# CPCIS_Connectors_P1_P6.net
KiCad netlist of a schematic drawn in Altium Designer
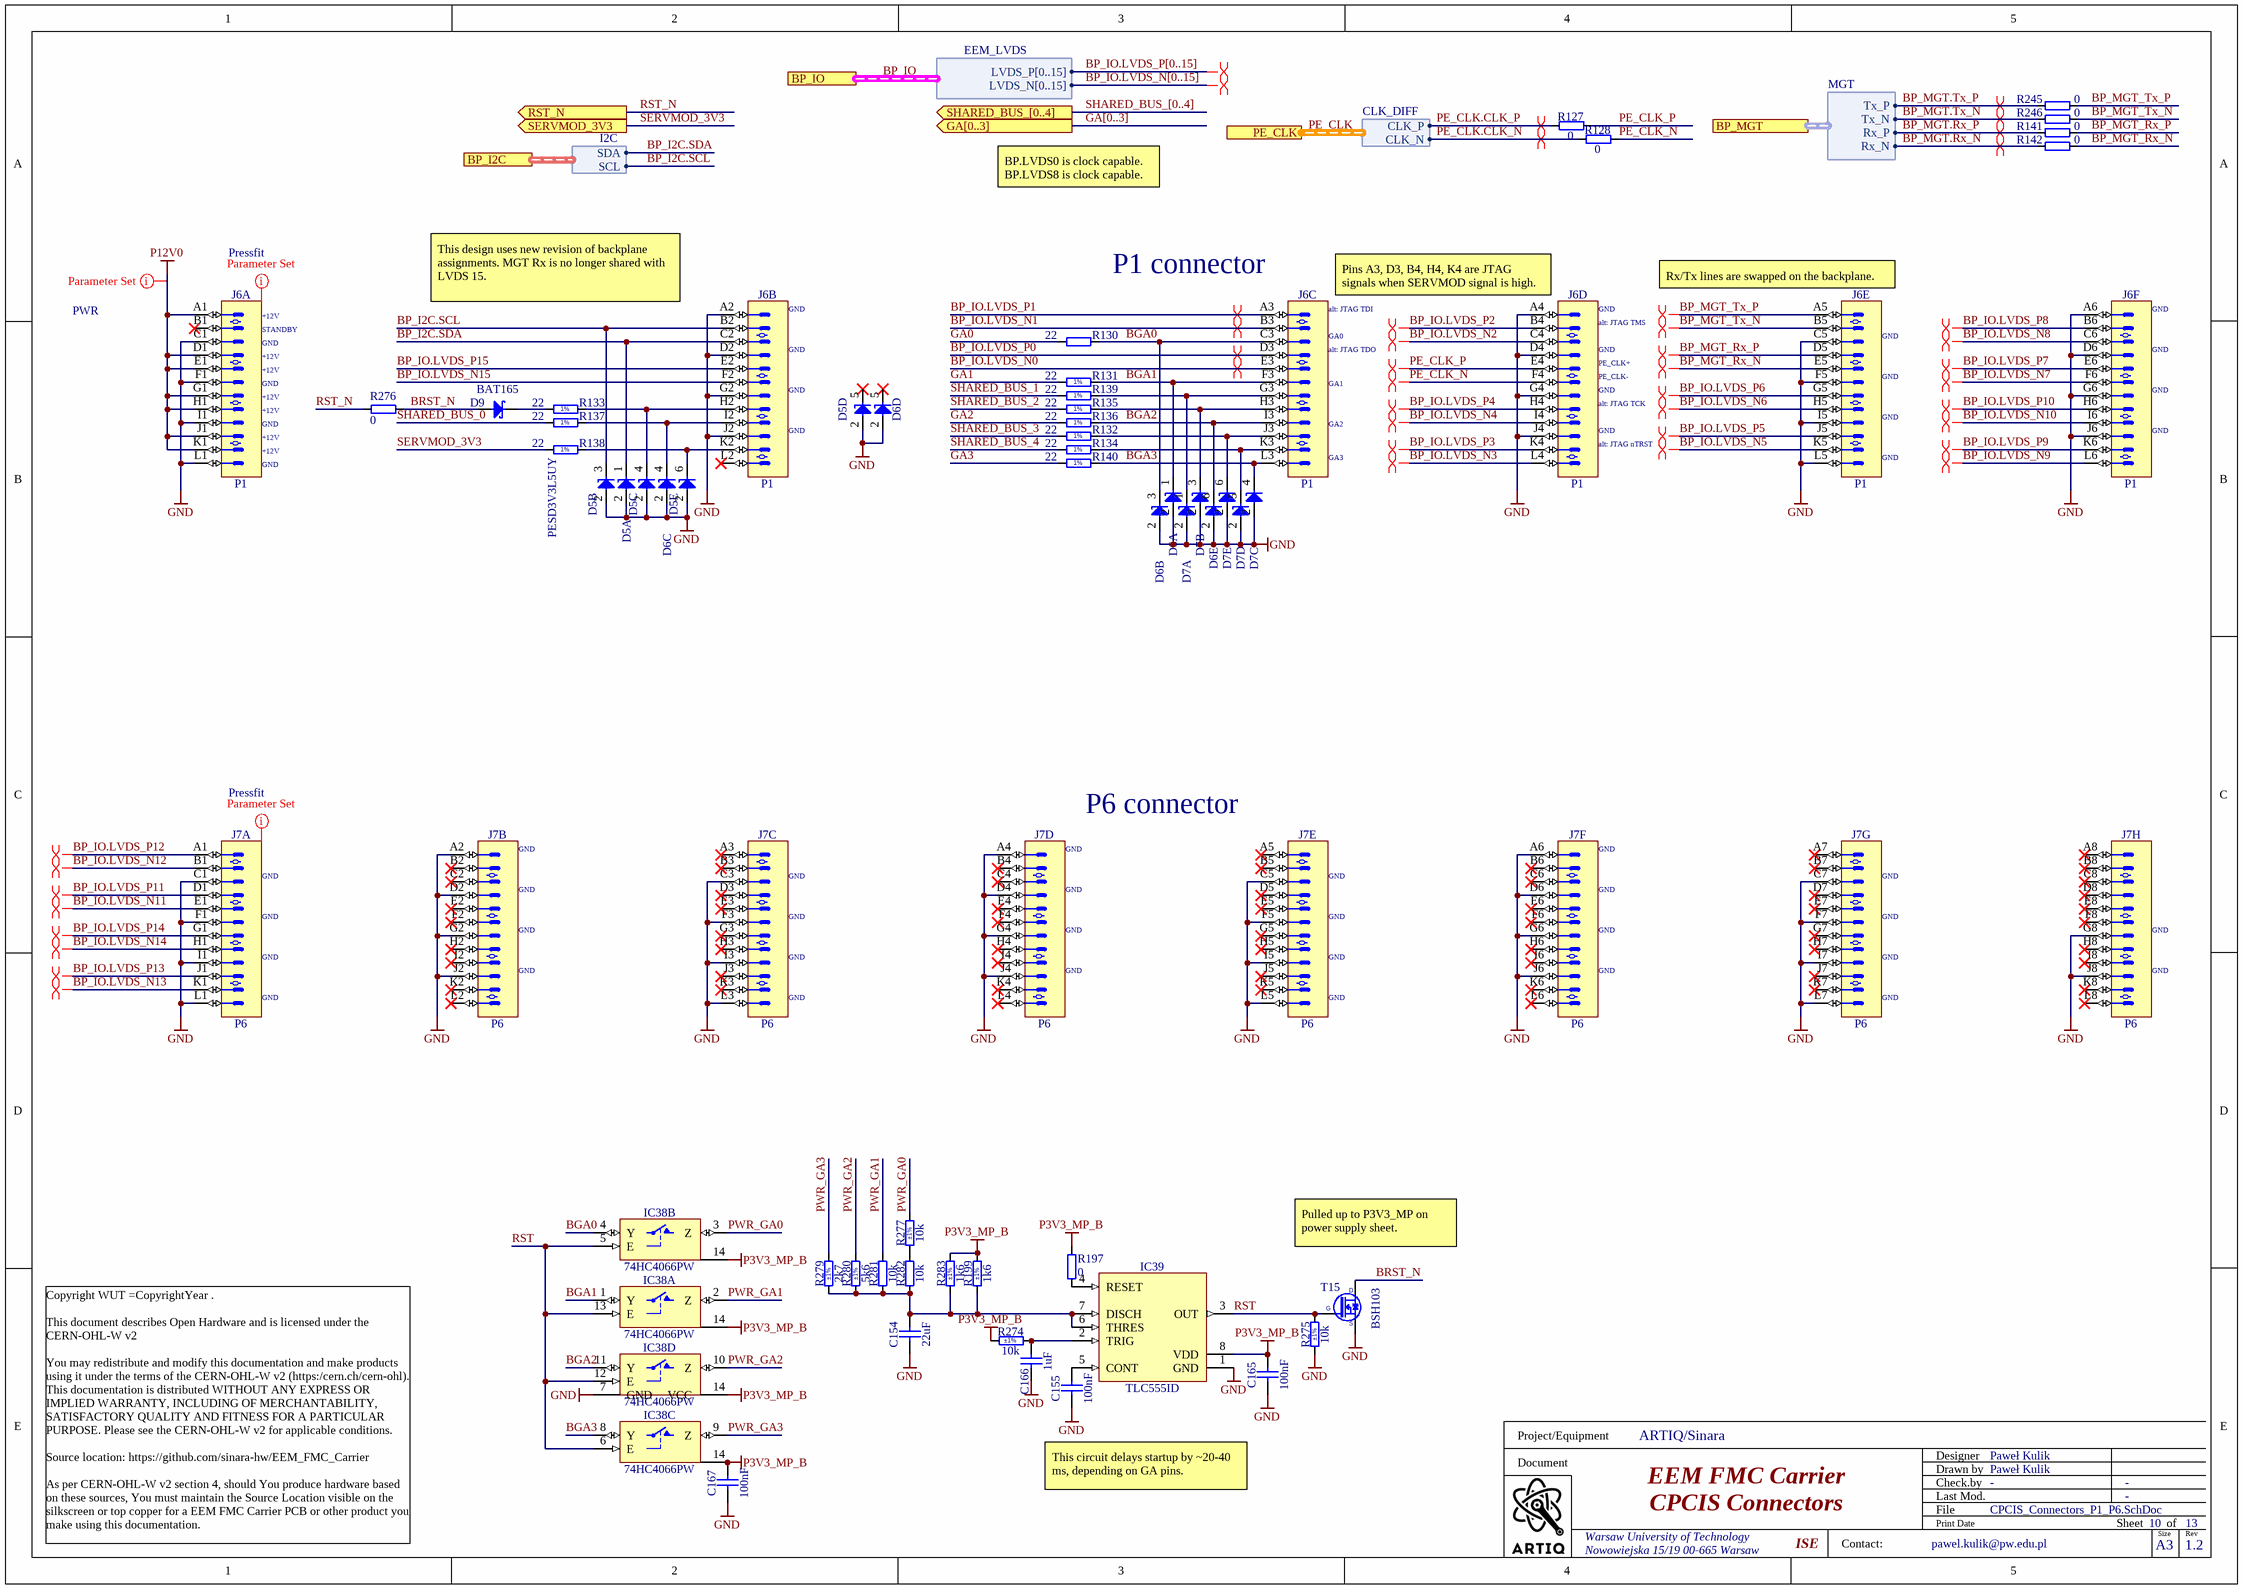
[diagram p0: CPCIS_Connectors_P1_P6.SchDoc]

(export (version "E")
  (design (tool "Eeschema 10.0.6"))
  (components
    (comp (ref "C154")
      (value "22uF")
      (footprint "CAPC1608X90N")
      (description "Non-polarised capacitor")
      (fields
        (field (name "MANUFACTURER") "GENERIC")
        (field (name "PART NUMBER") "CC0603_22UF_6.3V_20%_X5R")
        (field (name "AUTHOR") "CERN DEM JLC")
      )
      (libsource (lib "Capacitors") (part "Capacitor - non polarized"))
    )
    (comp (ref "C155")
      (value "100nF")
      (footprint "CAPC1005X55N")
      (description "Non-polarised capacitor")
      (fields
        (field (name "PART NUMBER") "CC0402_100NF_16V_10%_X5R")
        (field (name "VOLTAGE") "16V")
        (field (name "AUTHOR") "CERN DEM JLC")
      )
      (libsource (lib "Capacitors") (part "Capacitor - non polarized"))
    )
    (comp (ref "C165")
      (value "100nF")
      (footprint "CAPC1005X55N")
      (description "Non-polarised capacitor")
      (fields
        (field (name "PART NUMBER") "CC0402_100NF_16V_10%_X5R")
        (field (name "VOLTAGE") "16V")
        (field (name "AUTHOR") "CERN DEM JLC")
      )
      (libsource (lib "Capacitors") (part "Capacitor - non polarized"))
    )
    (comp (ref "C166")
      (value "1uF")
      (footprint "CAPC1005X55N")
      (description "Non-polarised capacitor")
      (fields
        (field (name "PART NUMBER") "CC0402_1UF_16V_10%_X5R")
        (field (name "VOLTAGE") "16V")
        (field (name "AUTHOR") "CERN DEM JLC")
      )
      (libsource (lib "Capacitors") (part "Capacitor - non polarized"))
    )
    (comp (ref "C167")
      (value "100nF")
      (footprint "CAPC1005X55N")
      (description "Non-polarised capacitor")
      (fields
        (field (name "PART NUMBER") "CC0402_100NF_16V_10%_X5R")
        (field (name "VOLTAGE") "16V")
        (field (name "AUTHOR") "CERN DEM JLC")
      )
      (libsource (lib "Capacitors") (part "Capacitor - non polarized"))
    )
    (comp (ref "D5")
      (value "PESD3V3L5UY")
      (footprint "SOT65P210X110-6N")
      (description "Fivefold ESD Protection Diode Arrays")
      (fields
        (field (name "VOLTAGE") "3.3V")
        (field (name "POWER") "200W")
        (field (name "AUTHOR") "CERN DEM WB")
      )
      (libsource (lib "ICs And Semiconductors") (part "PESD Array 5diodes 6pins Common anode2"))
    )
    (comp (ref "D6")
      (value "PESD3V3L5UY")
      (footprint "SOT65P210X110-6N")
      (description "Fivefold ESD Protection Diode Arrays")
      (fields
        (field (name "VOLTAGE") "3.3V")
        (field (name "POWER") "200W")
        (field (name "AUTHOR") "CERN DEM WB")
      )
      (libsource (lib "ICs And Semiconductors") (part "PESD Array 5diodes 6pins Common anode2"))
    )
    (comp (ref "D7")
      (value "PESD3V3L5UY")
      (footprint "SOT65P210X110-6N")
      (description "Fivefold ESD Protection Diode Arrays")
      (fields
        (field (name "VOLTAGE") "3.3V")
        (field (name "POWER") "200W")
        (field (name "AUTHOR") "CERN DEM WB")
      )
      (libsource (lib "ICs And Semiconductors") (part "PESD Array 5diodes 6pins Common anode2"))
    )
    (comp (ref "D9")
      (value "BAT165")
      (footprint "SOD2512X110N")
      (description "Schottky Diode")
      (fields
        (field (name "MANUFACTURER") "INFINEON")
        (field (name "VOLTAGE") "40V")
        (field (name "AUTHOR") "CERN DEM JLC")
      )
      (libsource (lib "ICs And Semiconductors") (part "Diode Schottky"))
    )
    (comp (ref "IC38")
      (value "74HC4066PW")
      (footprint "SOP65P640X110-14N")
      (fields (field (name "MANUFACTURER") "NXP SEMICONDUCTORS") (field (name "AUTHOR") "CERN DEM JLC"))
      (libsource (lib "ICs And Semiconductors") (part "4066"))
    )
    (comp (ref "IC39")
      (value "TLC555ID")
      (footprint "SOIC127P600X175-8N")
      (description "LinCMOS Timer")
      (fields (field (name "MANUFACTURER") "TEXAS INSTRUMENTS") (field (name "AUTHOR") "CERN DEM JMW"))
      (libsource (lib "ICs And Semiconductors") (part "TLC555"))
    )
    (comp (ref "J6")
      (value "P1")
      (footprint "AMPHENOL_10052825-101LF")
      (description "72 Contacts Header, 6 Columns, 4 Pairs per Column")
      (fields
        (field (name "PART NUMBER") "AMPHENOL_10052825-101LF")
        (field (name "MANUFACTURER") "AMPHENOL")
        (field (name "AUTHOR") "CERN DEM MR")
      )
      (libsource (lib "Connectors") (part "AMPHENOL_10052825-101LF"))
    )
    (comp (ref "J7")
      (value "P6")
      (footprint "AMPHENOL_10052838-101LF")
      (description "96 Contacts Header, 8 Columns, 4 Pairs per Column")
      (fields
        (field (name "PART NUMBER") "AMPHENOL_10052838-101LF")
        (field (name "MANUFACTURER") "AMPHENOL")
        (field (name "AUTHOR") "CERN DEM MR")
      )
      (libsource (lib "Connectors") (part "AMPHENOL_10052838-101LF"))
    )
    (comp (ref "R127")
      (value "0")
      (footprint "RESC0603X28N")
      (description "Resistor")
      (fields
        (field (name "PART NUMBER") "R0201_0R_JUMPER")
        (field (name "MANUFACTURER") "GENERIC")
        (field (name "AUTHOR") "CERN DEM JLC")
      )
      (libsource (lib "Resistors") (part "Resistor"))
    )
    (comp (ref "R128")
      (value "0")
      (footprint "RESC0603X28N")
      (description "Resistor")
      (fields
        (field (name "PART NUMBER") "R0201_0R_JUMPER")
        (field (name "MANUFACTURER") "GENERIC")
        (field (name "AUTHOR") "CERN DEM JLC")
      )
      (libsource (lib "Resistors") (part "Resistor"))
    )
    (comp (ref "R130")
      (value "22")
      (footprint "RESC1005X40N")
      (description "Resistor - 1%")
      (fields
        (field (name "PART NUMBER") "R0402_22R_1%_0.0625W_100PPM")
        (field (name "POWER") "0.0625W")
        (field (name "AUTHOR") "CERN DEM JLC")
      )
      (libsource (lib "Resistors") (part "Resistor - 1%"))
    )
    (comp (ref "R131")
      (value "22")
      (footprint "RESC1005X40N")
      (description "Resistor - 1%")
      (fields
        (field (name "PART NUMBER") "R0402_22R_1%_0.0625W_100PPM")
        (field (name "POWER") "0.0625W")
        (field (name "AUTHOR") "CERN DEM JLC")
      )
      (libsource (lib "Resistors") (part "Resistor - 1%"))
    )
    (comp (ref "R132")
      (value "22")
      (footprint "RESC1005X40N")
      (description "Resistor - 1%")
      (fields
        (field (name "PART NUMBER") "R0402_22R_1%_0.0625W_100PPM")
        (field (name "POWER") "0.0625W")
        (field (name "AUTHOR") "CERN DEM JLC")
      )
      (libsource (lib "Resistors") (part "Resistor - 1%"))
    )
    (comp (ref "R133")
      (value "22")
      (footprint "RESC1005X40N")
      (description "Resistor - 1%")
      (fields
        (field (name "PART NUMBER") "R0402_22R_1%_0.0625W_100PPM")
        (field (name "POWER") "0.0625W")
        (field (name "AUTHOR") "CERN DEM JLC")
      )
      (libsource (lib "Resistors") (part "Resistor - 1%"))
    )
    (comp (ref "R134")
      (value "22")
      (footprint "RESC1005X40N")
      (description "Resistor - 1%")
      (fields
        (field (name "PART NUMBER") "R0402_22R_1%_0.0625W_100PPM")
        (field (name "POWER") "0.0625W")
        (field (name "AUTHOR") "CERN DEM JLC")
      )
      (libsource (lib "Resistors") (part "Resistor - 1%"))
    )
    (comp (ref "R135")
      (value "22")
      (footprint "RESC1005X40N")
      (description "Resistor - 1%")
      (fields
        (field (name "PART NUMBER") "R0402_22R_1%_0.0625W_100PPM")
        (field (name "POWER") "0.0625W")
        (field (name "AUTHOR") "CERN DEM JLC")
      )
      (libsource (lib "Resistors") (part "Resistor - 1%"))
    )
    (comp (ref "R136")
      (value "22")
      (footprint "RESC1005X40N")
      (description "Resistor - 1%")
      (fields
        (field (name "PART NUMBER") "R0402_22R_1%_0.0625W_100PPM")
        (field (name "POWER") "0.0625W")
        (field (name "AUTHOR") "CERN DEM JLC")
      )
      (libsource (lib "Resistors") (part "Resistor - 1%"))
    )
    (comp (ref "R137")
      (value "22")
      (footprint "RESC1005X40N")
      (description "Resistor - 1%")
      (fields
        (field (name "PART NUMBER") "R0402_22R_1%_0.0625W_100PPM")
        (field (name "POWER") "0.0625W")
        (field (name "AUTHOR") "CERN DEM JLC")
      )
      (libsource (lib "Resistors") (part "Resistor - 1%"))
    )
    (comp (ref "R138")
      (value "22")
      (footprint "RESC1005X40N")
      (description "Resistor - 1%")
      (fields
        (field (name "PART NUMBER") "R0402_22R_1%_0.0625W_100PPM")
        (field (name "POWER") "0.0625W")
        (field (name "AUTHOR") "CERN DEM JLC")
      )
      (libsource (lib "Resistors") (part "Resistor - 1%"))
    )
    (comp (ref "R139")
      (value "22")
      (footprint "RESC1005X40N")
      (description "Resistor - 1%")
      (fields
        (field (name "PART NUMBER") "R0402_22R_1%_0.0625W_100PPM")
        (field (name "POWER") "0.0625W")
        (field (name "AUTHOR") "CERN DEM JLC")
      )
      (libsource (lib "Resistors") (part "Resistor - 1%"))
    )
    (comp (ref "R140")
      (value "22")
      (footprint "RESC1005X40N")
      (description "Resistor - 1%")
      (fields
        (field (name "PART NUMBER") "R0402_22R_1%_0.0625W_100PPM")
        (field (name "POWER") "0.0625W")
        (field (name "AUTHOR") "CERN DEM JLC")
      )
      (libsource (lib "Resistors") (part "Resistor - 1%"))
    )
    (comp (ref "R141")
      (value "0")
      (footprint "RESC0603X28N")
      (description "Resistor")
      (fields
        (field (name "PART NUMBER") "R0201_0R_JUMPER")
        (field (name "MANUFACTURER") "GENERIC")
        (field (name "AUTHOR") "CERN DEM JLC")
      )
      (libsource (lib "Resistors") (part "Resistor"))
    )
    (comp (ref "R142")
      (value "0")
      (footprint "RESC0603X28N")
      (description "Resistor")
      (fields
        (field (name "PART NUMBER") "R0201_0R_JUMPER")
        (field (name "MANUFACTURER") "GENERIC")
        (field (name "AUTHOR") "CERN DEM JLC")
      )
      (libsource (lib "Resistors") (part "Resistor"))
    )
    (comp (ref "R197")
      (value "0")
      (footprint "RESC1005X40N")
      (description "Resistor")
      (fields
        (field (name "PART NUMBER") "R0402_0R_JUMPER")
        (field (name "MANUFACTURER") "GENERIC")
        (field (name "AUTHOR") "CERN DEM JLC")
      )
      (libsource (lib "Resistors") (part "Resistor"))
    )
    (comp (ref "R199")
      (value "1k6")
      (footprint "RESC1005X40N")
      (description "Resistor - 1%")
      (fields
        (field (name "PART NUMBER") "R0402_1K6_1%_0.0625W_100PPM")
        (field (name "POWER") "0.0625W")
        (field (name "TOLERANCE") "±1%")
        (field (name "AUTHOR") "CERN DEM JLC")
      )
      (libsource (lib "Resistors") (part "Resistor - 1%"))
    )
    (comp (ref "R245")
      (value "0")
      (footprint "RESC0603X28N")
      (description "Resistor")
      (fields
        (field (name "PART NUMBER") "R0201_0R_JUMPER")
        (field (name "MANUFACTURER") "GENERIC")
        (field (name "AUTHOR") "CERN DEM JLC")
      )
      (libsource (lib "Resistors") (part "Resistor"))
    )
    (comp (ref "R246")
      (value "0")
      (footprint "RESC0603X28N")
      (description "Resistor")
      (fields
        (field (name "PART NUMBER") "R0201_0R_JUMPER")
        (field (name "MANUFACTURER") "GENERIC")
        (field (name "AUTHOR") "CERN DEM JLC")
      )
      (libsource (lib "Resistors") (part "Resistor"))
    )
    (comp (ref "R274")
      (value "10k")
      (footprint "RESC1005X40N")
      (description "Resistor - 1%")
      (fields
        (field (name "TOLERANCE") "±1%")
        (field (name "PART NUMBER") "R0402_10K_1%_0.0625W_100PPM")
        (field (name "POWER") "0.0625W")
        (field (name "AUTHOR") "CERN DEM JLC")
      )
      (libsource (lib "Resistors") (part "Resistor - 1%"))
    )
    (comp (ref "R275")
      (value "10k")
      (footprint "RESC1005X40N")
      (description "Resistor - 1%")
      (fields
        (field (name "TOLERANCE") "±1%")
        (field (name "PART NUMBER") "R0402_10K_1%_0.0625W_100PPM")
        (field (name "POWER") "0.0625W")
        (field (name "AUTHOR") "CERN DEM JLC")
      )
      (libsource (lib "Resistors") (part "Resistor - 1%"))
    )
    (comp (ref "R276")
      (value "0")
      (footprint "RESC1005X40N")
      (description "Resistor")
      (fields
        (field (name "PART NUMBER") "R0402_0R_JUMPER")
        (field (name "MANUFACTURER") "GENERIC")
        (field (name "AUTHOR") "CERN DEM JLC")
      )
      (libsource (lib "Resistors") (part "Resistor"))
    )
    (comp (ref "R277")
      (value "10k")
      (footprint "RESC1005X40N")
      (description "Resistor - 1%")
      (fields
        (field (name "PART NUMBER") "R0402_10K_1%_0.0625W_100PPM")
        (field (name "POWER") "0.0625W")
        (field (name "TOLERANCE") "±1%")
        (field (name "AUTHOR") "CERN DEM JLC")
      )
      (libsource (lib "Resistors") (part "Resistor - 1%"))
    )
    (comp (ref "R279")
      (value "2k7")
      (footprint "RESC1608X55N")
      (description "Resistor - 1%")
      (fields
        (field (name "PART NUMBER") "R0603_2K7_1%_0.1W_100PPM")
        (field (name "POWER") "0.1W")
        (field (name "TOLERANCE") "±1%")
        (field (name "AUTHOR") "CERN DEM JLC")
      )
      (libsource (lib "Resistors") (part "Resistor - 1%"))
    )
    (comp (ref "R280")
      (value "5k6")
      (footprint "RESC1005X40N")
      (description "Resistor - 1%")
      (fields
        (field (name "PART NUMBER") "R0402_5K6_1%_0.0625W_100PPM")
        (field (name "POWER") "0.0625W")
        (field (name "TOLERANCE") "±1%")
        (field (name "AUTHOR") "CERN DEM JLC")
      )
      (libsource (lib "Resistors") (part "Resistor - 1%"))
    )
    (comp (ref "R281")
      (value "10k")
      (footprint "RESC1005X40N")
      (description "Resistor - 1%")
      (fields
        (field (name "PART NUMBER") "R0402_10K_1%_0.0625W_100PPM")
        (field (name "POWER") "0.0625W")
        (field (name "AUTHOR") "CERN DEM JLC")
      )
      (libsource (lib "Resistors") (part "Resistor - 1%"))
    )
    (comp (ref "R282")
      (value "10k")
      (footprint "RESC1005X40N")
      (description "Resistor - 1%")
      (fields
        (field (name "PART NUMBER") "R0402_10K_1%_0.0625W_100PPM")
        (field (name "POWER") "0.0625W")
        (field (name "AUTHOR") "CERN DEM JLC")
      )
      (libsource (lib "Resistors") (part "Resistor - 1%"))
    )
    (comp (ref "R283")
      (value "1k6")
      (footprint "RESC1005X40N")
      (description "Resistor - 1%")
      (fields
        (field (name "PART NUMBER") "R0402_1K6_1%_0.0625W_100PPM")
        (field (name "POWER") "0.0625W")
        (field (name "TOLERANCE") "±1%")
        (field (name "AUTHOR") "CERN DEM JLC")
      )
      (libsource (lib "Resistors") (part "Resistor - 1%"))
    )
    (comp (ref "T15")
      (value "BSH103")
      (footprint "SOT95P230X110-3N")
      (description "N-CHANNEL MOSFET WITH DIODE")
      (fields (field (name "MANUFACTURER") "NEXPERIA") (field (name "AUTHOR") "CERN DEM JLC"))
      (libsource (lib "ICs And Semiconductors") (part "N-MOSFET-D 1G 2S 3D"))
    )
  )
  (nets
    (net (code "5") (name "/BGA0") (class "Default")
      (node (ref "D6") (pin "3") (pinfunction "C_3") (pintype "passive"))
      (node (ref "IC38") (pin "4") (pinfunction "Y_4") (pintype "bidirectional"))
      (node (ref "J6") (pin "C3") (pinfunction "C3_C3") (pintype "bidirectional"))
      (node (ref "R130") (pin "2") (pinfunction "2_2") (pintype "passive"))
    )
    (net (code "6") (name "/BGA1") (class "Default")
      (node (ref "D6") (pin "1") (pinfunction "C_1") (pintype "passive"))
      (node (ref "IC38") (pin "1") (pinfunction "Y_1") (pintype "bidirectional"))
      (node (ref "J6") (pin "F3") (pinfunction "F3_F3") (pintype "bidirectional"))
      (node (ref "R131") (pin "2") (pinfunction "2_2") (pintype "passive"))
    )
    (net (code "7") (name "/BGA2") (class "Default")
      (node (ref "D6") (pin "6") (pinfunction "C_6") (pintype "passive"))
      (node (ref "IC38") (pin "11") (pinfunction "Y_11") (pintype "bidirectional"))
      (node (ref "J6") (pin "I3") (pinfunction "I3_I3") (pintype "bidirectional"))
      (node (ref "R136") (pin "2") (pinfunction "2_2") (pintype "passive"))
    )
    (net (code "8") (name "/BGA3") (class "Default")
      (node (ref "D7") (pin "4") (pinfunction "C_4") (pintype "passive"))
      (node (ref "IC38") (pin "8") (pinfunction "Y_8") (pintype "bidirectional"))
      (node (ref "J6") (pin "L3") (pinfunction "L3_L3") (pintype "bidirectional"))
      (node (ref "R140") (pin "2") (pinfunction "2_2") (pintype "passive"))
    )
    (net (code "9") (name "/BP_I2C.SCL") (class "Default")
      (node (ref "D5") (pin "3") (pinfunction "C_3") (pintype "passive"))
      (node (ref "J6") (pin "B2") (pinfunction "B2_B2") (pintype "bidirectional"))
    )
    (net (code "10") (name "/BP_I2C.SDA") (class "Default")
      (node (ref "D5") (pin "1") (pinfunction "C_1") (pintype "passive"))
      (node (ref "J6") (pin "C2") (pinfunction "C2_C2") (pintype "bidirectional"))
    )
    (net (code "11") (name "/BP_IO.LVDS_N0") (class "Default")
      (node (ref "J6") (pin "E3") (pinfunction "E3_E3") (pintype "bidirectional"))
    )
    (net (code "12") (name "/BP_IO.LVDS_N1") (class "Default")
      (node (ref "J6") (pin "B3") (pinfunction "B3_B3") (pintype "bidirectional"))
    )
    (net (code "13") (name "/BP_IO.LVDS_N2") (class "Default")
      (node (ref "J6") (pin "C4") (pinfunction "C4_C4") (pintype "bidirectional"))
    )
    (net (code "14") (name "/BP_IO.LVDS_N3") (class "Default")
      (node (ref "J6") (pin "L4") (pinfunction "L4_L4") (pintype "bidirectional"))
    )
    (net (code "15") (name "/BP_IO.LVDS_N4") (class "Default")
      (node (ref "J6") (pin "I4") (pinfunction "I4_I4") (pintype "bidirectional"))
    )
    (net (code "16") (name "/BP_IO.LVDS_N5") (class "Default")
      (node (ref "J6") (pin "K5") (pinfunction "K5_K5") (pintype "bidirectional"))
    )
    (net (code "17") (name "/BP_IO.LVDS_N6") (class "Default")
      (node (ref "J6") (pin "H5") (pinfunction "H5_H5") (pintype "bidirectional"))
    )
    (net (code "18") (name "/BP_IO.LVDS_N7") (class "Default")
      (node (ref "J6") (pin "F6") (pinfunction "F6_F6") (pintype "bidirectional"))
    )
    (net (code "19") (name "/BP_IO.LVDS_N8") (class "Default")
      (node (ref "J6") (pin "C6") (pinfunction "C6_C6") (pintype "bidirectional"))
    )
    (net (code "20") (name "/BP_IO.LVDS_N9") (class "Default")
      (node (ref "J6") (pin "L6") (pinfunction "L6_L6") (pintype "bidirectional"))
    )
    (net (code "21") (name "/BP_IO.LVDS_N10") (class "Default")
      (node (ref "J6") (pin "I6") (pinfunction "I6_I6") (pintype "bidirectional"))
    )
    (net (code "22") (name "/BP_IO.LVDS_N11") (class "Default")
      (node (ref "J7") (pin "E1") (pinfunction "E1_E1") (pintype "bidirectional"))
    )
    (net (code "23") (name "/BP_IO.LVDS_N12") (class "Default")
      (node (ref "J7") (pin "B1") (pinfunction "B1_B1") (pintype "bidirectional"))
    )
    (net (code "24") (name "/BP_IO.LVDS_N13") (class "Default")
      (node (ref "J7") (pin "K1") (pinfunction "K1_K1") (pintype "bidirectional"))
    )
    (net (code "25") (name "/BP_IO.LVDS_N14") (class "Default")
      (node (ref "J7") (pin "H1") (pinfunction "H1_H1") (pintype "bidirectional"))
    )
    (net (code "26") (name "/BP_IO.LVDS_N15") (class "Default")
      (node (ref "J6") (pin "F2") (pinfunction "F2_F2") (pintype "bidirectional"))
    )
    (net (code "28") (name "/BP_IO.LVDS_P0") (class "Default")
      (node (ref "J6") (pin "D3") (pinfunction "D3_D3") (pintype "bidirectional"))
    )
    (net (code "29") (name "/BP_IO.LVDS_P1") (class "Default")
      (node (ref "J6") (pin "A3") (pinfunction "A3_A3") (pintype "bidirectional"))
    )
    (net (code "30") (name "/BP_IO.LVDS_P2") (class "Default")
      (node (ref "J6") (pin "B4") (pinfunction "B4_B4") (pintype "bidirectional"))
    )
    (net (code "31") (name "/BP_IO.LVDS_P3") (class "Default")
      (node (ref "J6") (pin "K4") (pinfunction "K4_K4") (pintype "bidirectional"))
    )
    (net (code "32") (name "/BP_IO.LVDS_P4") (class "Default")
      (node (ref "J6") (pin "H4") (pinfunction "H4_H4") (pintype "bidirectional"))
    )
    (net (code "33") (name "/BP_IO.LVDS_P5") (class "Default")
      (node (ref "J6") (pin "J5") (pinfunction "J5_J5") (pintype "bidirectional"))
    )
    (net (code "34") (name "/BP_IO.LVDS_P6") (class "Default")
      (node (ref "J6") (pin "G5") (pinfunction "G5_G5") (pintype "bidirectional"))
    )
    (net (code "35") (name "/BP_IO.LVDS_P7") (class "Default")
      (node (ref "J6") (pin "E6") (pinfunction "E6_E6") (pintype "bidirectional"))
    )
    (net (code "36") (name "/BP_IO.LVDS_P8") (class "Default")
      (node (ref "J6") (pin "B6") (pinfunction "B6_B6") (pintype "bidirectional"))
    )
    (net (code "37") (name "/BP_IO.LVDS_P9") (class "Default")
      (node (ref "J6") (pin "K6") (pinfunction "K6_K6") (pintype "bidirectional"))
    )
    (net (code "38") (name "/BP_IO.LVDS_P10") (class "Default")
      (node (ref "J6") (pin "H6") (pinfunction "H6_H6") (pintype "bidirectional"))
    )
    (net (code "39") (name "/BP_IO.LVDS_P11") (class "Default")
      (node (ref "J7") (pin "D1") (pinfunction "D1_D1") (pintype "bidirectional"))
    )
    (net (code "40") (name "/BP_IO.LVDS_P12") (class "Default")
      (node (ref "J7") (pin "A1") (pinfunction "A1_A1") (pintype "bidirectional"))
    )
    (net (code "41") (name "/BP_IO.LVDS_P13") (class "Default")
      (node (ref "J7") (pin "J1") (pinfunction "J1_J1") (pintype "bidirectional"))
    )
    (net (code "42") (name "/BP_IO.LVDS_P14") (class "Default")
      (node (ref "J7") (pin "G1") (pinfunction "G1_G1") (pintype "bidirectional"))
    )
    (net (code "43") (name "/BP_IO.LVDS_P15") (class "Default")
      (node (ref "J6") (pin "E2") (pinfunction "E2_E2") (pintype "bidirectional"))
    )
    (net (code "44") (name "/BP_MGT.Rx_N") (class "Default")
      (node (ref "R142") (pin "1") (pinfunction "1_1") (pintype "passive"))
    )
    (net (code "45") (name "/BP_MGT.Rx_P") (class "Default")
      (node (ref "R141") (pin "1") (pinfunction "1_1") (pintype "passive"))
    )
    (net (code "46") (name "/BP_MGT.Tx_N") (class "Default")
      (node (ref "R246") (pin "1") (pinfunction "1_1") (pintype "passive"))
    )
    (net (code "47") (name "/BP_MGT.Tx_P") (class "Default")
      (node (ref "R245") (pin "1") (pinfunction "1_1") (pintype "passive"))
    )
    (net (code "48") (name "/BP_MGT_Rx_N") (class "Default")
      (node (ref "J6") (pin "E5") (pinfunction "E5_E5") (pintype "bidirectional"))
      (node (ref "R142") (pin "2") (pinfunction "2_2") (pintype "passive"))
    )
    (net (code "49") (name "/BP_MGT_Rx_P") (class "Default")
      (node (ref "J6") (pin "D5") (pinfunction "D5_D5") (pintype "bidirectional"))
      (node (ref "R141") (pin "2") (pinfunction "2_2") (pintype "passive"))
    )
    (net (code "50") (name "/BP_MGT_Tx_N") (class "Default")
      (node (ref "J6") (pin "B5") (pinfunction "B5_B5") (pintype "bidirectional"))
      (node (ref "R246") (pin "2") (pinfunction "2_2") (pintype "passive"))
    )
    (net (code "51") (name "/BP_MGT_Tx_P") (class "Default")
      (node (ref "J6") (pin "A5") (pinfunction "A5_A5") (pintype "bidirectional"))
      (node (ref "R245") (pin "2") (pinfunction "2_2") (pintype "passive"))
    )
    (net (code "52") (name "/BRST_N") (class "Default")
      (node (ref "D9") (pin "2") (pinfunction "A_2") (pintype "passive"))
      (node (ref "R276") (pin "1") (pinfunction "1_1") (pintype "passive"))
      (node (ref "T15") (pin "3") (pinfunction "D_3") (pintype "passive"))
    )
    (net (code "53") (name "/GA0") (class "Default")
      (node (ref "R130") (pin "1") (pinfunction "1_1") (pintype "passive"))
    )
    (net (code "54") (name "/GA1") (class "Default")
      (node (ref "R131") (pin "1") (pinfunction "1_1") (pintype "passive"))
    )
    (net (code "55") (name "/GA2") (class "Default")
      (node (ref "R136") (pin "1") (pinfunction "1_1") (pintype "passive"))
    )
    (net (code "56") (name "/GA3") (class "Default")
      (node (ref "R140") (pin "1") (pinfunction "1_1") (pintype "passive"))
    )
    (net (code "58") (name "/PE_CLK.CLK_N") (class "Default")
      (node (ref "R128") (pin "1") (pinfunction "1_1") (pintype "passive"))
    )
    (net (code "59") (name "/PE_CLK.CLK_P") (class "Default")
      (node (ref "R127") (pin "1") (pinfunction "1_1") (pintype "passive"))
    )
    (net (code "60") (name "/PE_CLK_N") (class "Default")
      (node (ref "J6") (pin "F4") (pinfunction "F4_F4") (pintype "bidirectional"))
      (node (ref "R128") (pin "2") (pinfunction "2_2") (pintype "passive"))
    )
    (net (code "61") (name "/PE_CLK_P") (class "Default")
      (node (ref "J6") (pin "E4") (pinfunction "E4_E4") (pintype "bidirectional"))
      (node (ref "R127") (pin "2") (pinfunction "2_2") (pintype "passive"))
    )
    (net (code "63") (name "/PWR_GA0") (class "Default")
      (node (ref "IC38") (pin "3") (pinfunction "Z_3") (pintype "bidirectional"))
      (node (ref "R277") (pin "2") (pinfunction "2_2") (pintype "passive"))
    )
    (net (code "64") (name "/PWR_GA1") (class "Default")
      (node (ref "IC38") (pin "2") (pinfunction "Z_2") (pintype "bidirectional"))
      (node (ref "R281") (pin "2") (pinfunction "2_2") (pintype "passive"))
    )
    (net (code "65") (name "/PWR_GA2") (class "Default")
      (node (ref "IC38") (pin "10") (pinfunction "Z_10") (pintype "bidirectional"))
      (node (ref "R280") (pin "2") (pinfunction "2_2") (pintype "passive"))
    )
    (net (code "66") (name "/PWR_GA3") (class "Default")
      (node (ref "IC38") (pin "9") (pinfunction "Z_9") (pintype "bidirectional"))
      (node (ref "R279") (pin "2") (pinfunction "2_2") (pintype "passive"))
    )
    (net (code "67") (name "/RST") (class "Default")
      (node (ref "IC38") (pin "12") (pinfunction "E_12") (pintype "input"))
      (node (ref "IC38") (pin "13") (pinfunction "E_13") (pintype "input"))
      (node (ref "IC38") (pin "5") (pinfunction "E_5") (pintype "input"))
      (node (ref "IC38") (pin "6") (pinfunction "E_6") (pintype "input"))
      (node (ref "IC39") (pin "3") (pinfunction "OUT_3") (pintype "output"))
      (node (ref "R275") (pin "2") (pinfunction "2_2") (pintype "passive"))
      (node (ref "T15") (pin "1") (pinfunction "G_1") (pintype "passive"))
    )
    (net (code "68") (name "/RST_N") (class "Default")
      (node (ref "R276") (pin "2") (pinfunction "2_2") (pintype "passive"))
    )
    (net (code "69") (name "/SERVMOD_3V3") (class "Default")
      (node (ref "R138") (pin "1") (pinfunction "1_1") (pintype "passive"))
    )
    (net (code "70") (name "/SHARED_BUS_0") (class "Default")
      (node (ref "R137") (pin "1") (pinfunction "1_1") (pintype "passive"))
    )
    (net (code "71") (name "/SHARED_BUS_1") (class "Default")
      (node (ref "R139") (pin "1") (pinfunction "1_1") (pintype "passive"))
    )
    (net (code "72") (name "/SHARED_BUS_2") (class "Default")
      (node (ref "R135") (pin "1") (pinfunction "1_1") (pintype "passive"))
    )
    (net (code "73") (name "/SHARED_BUS_3") (class "Default")
      (node (ref "R132") (pin "1") (pinfunction "1_1") (pintype "passive"))
    )
    (net (code "74") (name "/SHARED_BUS_4") (class "Default")
      (node (ref "R134") (pin "1") (pinfunction "1_1") (pintype "passive"))
    )
    (net (code "80") (name "GND") (class "Default")
      (node (ref "C154") (pin "1") (pinfunction "1_1") (pintype "passive"))
      (node (ref "C155") (pin "1") (pinfunction "1_1") (pintype "passive"))
      (node (ref "C165") (pin "1") (pinfunction "1_1") (pintype "passive"))
      (node (ref "C166") (pin "1") (pinfunction "1_1") (pintype "passive"))
      (node (ref "C167") (pin "1") (pinfunction "1_1") (pintype "passive"))
      (node (ref "D5") (pin "2") (pinfunction "A_2") (pintype "passive"))
      (node (ref "D6") (pin "2") (pinfunction "A_2") (pintype "passive"))
      (node (ref "D7") (pin "2") (pinfunction "A_2") (pintype "passive"))
      (node (ref "IC38") (pin "7") (pinfunction "GND_7") (pintype "power_in"))
      (node (ref "IC39") (pin "1") (pinfunction "GND_1") (pintype "power_in"))
      (node (ref "J6") (pin "A2") (pinfunction "A2_A2") (pintype "bidirectional"))
      (node (ref "J6") (pin "A4") (pinfunction "A4_A4") (pintype "bidirectional"))
      (node (ref "J6") (pin "A6") (pinfunction "A6_A6") (pintype "bidirectional"))
      (node (ref "J6") (pin "C1") (pinfunction "C1_C1") (pintype "bidirectional"))
      (node (ref "J6") (pin "C5") (pinfunction "C5_C5") (pintype "bidirectional"))
      (node (ref "J6") (pin "D2") (pinfunction "D2_D2") (pintype "bidirectional"))
      (node (ref "J6") (pin "D4") (pinfunction "D4_D4") (pintype "bidirectional"))
      (node (ref "J6") (pin "D6") (pinfunction "D6_D6") (pintype "bidirectional"))
      (node (ref "J6") (pin "F1") (pinfunction "F1_F1") (pintype "bidirectional"))
      (node (ref "J6") (pin "F5") (pinfunction "F5_F5") (pintype "bidirectional"))
      (node (ref "J6") (pin "G2") (pinfunction "G2_G2") (pintype "bidirectional"))
      (node (ref "J6") (pin "G4") (pinfunction "G4_G4") (pintype "bidirectional"))
      (node (ref "J6") (pin "G6") (pinfunction "G6_G6") (pintype "bidirectional"))
      (node (ref "J6") (pin "I1") (pinfunction "I1_I1") (pintype "bidirectional"))
      (node (ref "J6") (pin "I5") (pinfunction "I5_I5") (pintype "bidirectional"))
      (node (ref "J6") (pin "J2") (pinfunction "J2_J2") (pintype "bidirectional"))
      (node (ref "J6") (pin "J4") (pinfunction "J4_J4") (pintype "bidirectional"))
      (node (ref "J6") (pin "J6") (pinfunction "J6_J6") (pintype "bidirectional"))
      (node (ref "J6") (pin "L1") (pinfunction "L1_L1") (pintype "bidirectional"))
      (node (ref "J6") (pin "L5") (pinfunction "L5_L5") (pintype "bidirectional"))
      (node (ref "J7") (pin "A2") (pinfunction "A2_A2") (pintype "bidirectional"))
      (node (ref "J7") (pin "A4") (pinfunction "A4_A4") (pintype "bidirectional"))
      (node (ref "J7") (pin "A6") (pinfunction "A6_A6") (pintype "bidirectional"))
      (node (ref "J7") (pin "C1") (pinfunction "C1_C1") (pintype "bidirectional"))
      (node (ref "J7") (pin "C3") (pinfunction "C3_C3") (pintype "bidirectional"))
      (node (ref "J7") (pin "C5") (pinfunction "C5_C5") (pintype "bidirectional"))
      (node (ref "J7") (pin "C7") (pinfunction "C7_C7") (pintype "bidirectional"))
      (node (ref "J7") (pin "D2") (pinfunction "D2_D2") (pintype "bidirectional"))
      (node (ref "J7") (pin "D4") (pinfunction "D4_D4") (pintype "bidirectional"))
      (node (ref "J7") (pin "D6") (pinfunction "D6_D6") (pintype "bidirectional"))
      (node (ref "J7") (pin "F1") (pinfunction "F1_F1") (pintype "bidirectional"))
      (node (ref "J7") (pin "F3") (pinfunction "F3_F3") (pintype "bidirectional"))
      (node (ref "J7") (pin "F5") (pinfunction "F5_F5") (pintype "bidirectional"))
      (node (ref "J7") (pin "F7") (pinfunction "F7_F7") (pintype "bidirectional"))
      (node (ref "J7") (pin "G2") (pinfunction "G2_G2") (pintype "bidirectional"))
      (node (ref "J7") (pin "G4") (pinfunction "G4_G4") (pintype "bidirectional"))
      (node (ref "J7") (pin "G6") (pinfunction "G6_G6") (pintype "bidirectional"))
      (node (ref "J7") (pin "G8") (pinfunction "G8_G8") (pintype "bidirectional"))
      (node (ref "J7") (pin "I1") (pinfunction "I1_I1") (pintype "bidirectional"))
      (node (ref "J7") (pin "I3") (pinfunction "I3_I3") (pintype "bidirectional"))
      (node (ref "J7") (pin "I5") (pinfunction "I5_I5") (pintype "bidirectional"))
      (node (ref "J7") (pin "I7") (pinfunction "I7_I7") (pintype "bidirectional"))
      (node (ref "J7") (pin "J2") (pinfunction "J2_J2") (pintype "bidirectional"))
      (node (ref "J7") (pin "J4") (pinfunction "J4_J4") (pintype "bidirectional"))
      (node (ref "J7") (pin "J6") (pinfunction "J6_J6") (pintype "bidirectional"))
      (node (ref "J7") (pin "J8") (pinfunction "J8_J8") (pintype "bidirectional"))
      (node (ref "J7") (pin "L1") (pinfunction "L1_L1") (pintype "bidirectional"))
      (node (ref "J7") (pin "L3") (pinfunction "L3_L3") (pintype "bidirectional"))
      (node (ref "J7") (pin "L5") (pinfunction "L5_L5") (pintype "bidirectional"))
      (node (ref "J7") (pin "L7") (pinfunction "L7_L7") (pintype "bidirectional"))
      (node (ref "R275") (pin "1") (pinfunction "1_1") (pintype "passive"))
      (node (ref "T15") (pin "2") (pinfunction "S_2") (pintype "passive"))
    )
    (net (code "81") (name "Net-(D5C-C)") (class "Default")
      (node (ref "D5") (pin "4") (pinfunction "C_4") (pintype "passive"))
      (node (ref "J6") (pin "H2") (pinfunction "H2_H2") (pintype "bidirectional"))
      (node (ref "R133") (pin "2") (pinfunction "2_2") (pintype "passive"))
    )
    (net (code "82") (name "Net-(D5E-C)") (class "Default")
      (node (ref "D5") (pin "6") (pinfunction "C_6") (pintype "passive"))
      (node (ref "J6") (pin "K2") (pinfunction "K2_K2") (pintype "bidirectional"))
      (node (ref "R138") (pin "2") (pinfunction "2_2") (pintype "passive"))
    )
    (net (code "83") (name "Net-(D6C-C)") (class "Default")
      (node (ref "D6") (pin "4") (pinfunction "C_4") (pintype "passive"))
      (node (ref "J6") (pin "I2") (pinfunction "I2_I2") (pintype "bidirectional"))
      (node (ref "R137") (pin "2") (pinfunction "2_2") (pintype "passive"))
    )
    (net (code "84") (name "Net-(D7A-C)") (class "Default")
      (node (ref "D7") (pin "1") (pinfunction "C_1") (pintype "passive"))
      (node (ref "J6") (pin "G3") (pinfunction "G3_G3") (pintype "bidirectional"))
      (node (ref "R139") (pin "2") (pinfunction "2_2") (pintype "passive"))
    )
    (net (code "85") (name "Net-(D7B-C)") (class "Default")
      (node (ref "D7") (pin "3") (pinfunction "C_3") (pintype "passive"))
      (node (ref "J6") (pin "H3") (pinfunction "H3_H3") (pintype "bidirectional"))
      (node (ref "R135") (pin "2") (pinfunction "2_2") (pintype "passive"))
    )
    (net (code "86") (name "Net-(D7D-C)") (class "Default")
      (node (ref "D7") (pin "5") (pinfunction "C_5") (pintype "passive"))
      (node (ref "J6") (pin "K3") (pinfunction "K3_K3") (pintype "bidirectional"))
      (node (ref "R134") (pin "2") (pinfunction "2_2") (pintype "passive"))
    )
    (net (code "87") (name "Net-(D7E-C)") (class "Default")
      (node (ref "D7") (pin "6") (pinfunction "C_6") (pintype "passive"))
      (node (ref "J6") (pin "J3") (pinfunction "J3_J3") (pintype "bidirectional"))
      (node (ref "R132") (pin "2") (pinfunction "2_2") (pintype "passive"))
    )
    (net (code "88") (name "Net-(D9-C)") (class "Default")
      (node (ref "D9") (pin "1") (pinfunction "C_1") (pintype "passive"))
      (node (ref "R133") (pin "1") (pinfunction "1_1") (pintype "passive"))
    )
    (net (code "89") (name "Net-(IC39-CONT)") (class "Default")
      (node (ref "C155") (pin "2") (pinfunction "2_2") (pintype "passive"))
      (node (ref "IC39") (pin "5") (pinfunction "CONT_5") (pintype "input"))
    )
    (net (code "90") (name "Net-(IC39-DISCH)") (class "Default")
      (node (ref "C154") (pin "2") (pinfunction "2_2") (pintype "passive"))
      (node (ref "IC39") (pin "6") (pinfunction "THRES_6") (pintype "input"))
      (node (ref "IC39") (pin "7") (pinfunction "DISCH_7") (pintype "input"))
      (node (ref "R199") (pin "1") (pinfunction "1_1") (pintype "passive"))
      (node (ref "R279") (pin "1") (pinfunction "1_1") (pintype "passive"))
      (node (ref "R280") (pin "1") (pinfunction "1_1") (pintype "passive"))
      (node (ref "R281") (pin "1") (pinfunction "1_1") (pintype "passive"))
      (node (ref "R282") (pin "1") (pinfunction "1_1") (pintype "passive"))
      (node (ref "R283") (pin "1") (pinfunction "1_1") (pintype "passive"))
    )
    (net (code "91") (name "Net-(IC39-RESET)") (class "Default")
      (node (ref "IC39") (pin "4") (pinfunction "RESET_4") (pintype "input"))
      (node (ref "R197") (pin "1") (pinfunction "1_1") (pintype "passive"))
    )
    (net (code "92") (name "Net-(IC39-TRIG)") (class "Default")
      (node (ref "C166") (pin "2") (pinfunction "2_2") (pintype "passive"))
      (node (ref "IC39") (pin "2") (pinfunction "TRIG_2") (pintype "input"))
      (node (ref "R274") (pin "2") (pinfunction "2_2") (pintype "passive"))
    )
    (net (code "93") (name "Net-(R277-Pad1)") (class "Default")
      (node (ref "R277") (pin "1") (pinfunction "1_1") (pintype "passive"))
      (node (ref "R282") (pin "2") (pinfunction "2_2") (pintype "passive"))
    )
    (net (code "94") (name "P3V3_MP_B") (class "Default")
      (node (ref "C165") (pin "2") (pinfunction "2_2") (pintype "passive"))
      (node (ref "C167") (pin "2") (pinfunction "2_2") (pintype "passive"))
      (node (ref "IC38") (pin "14") (pinfunction "VCC_14") (pintype "power_in"))
      (node (ref "IC39") (pin "8") (pinfunction "VDD_8") (pintype "power_in"))
      (node (ref "R197") (pin "2") (pinfunction "2_2") (pintype "passive"))
      (node (ref "R199") (pin "2") (pinfunction "2_2") (pintype "passive"))
      (node (ref "R274") (pin "1") (pinfunction "1_1") (pintype "passive"))
      (node (ref "R283") (pin "2") (pinfunction "2_2") (pintype "passive"))
    )
    (net (code "95") (name "P12V0") (class "Default")
      (node (ref "J6") (pin "A1") (pinfunction "A1_A1") (pintype "bidirectional"))
      (node (ref "J6") (pin "D1") (pinfunction "D1_D1") (pintype "bidirectional"))
      (node (ref "J6") (pin "E1") (pinfunction "E1_E1") (pintype "bidirectional"))
      (node (ref "J6") (pin "G1") (pinfunction "G1_G1") (pintype "bidirectional"))
      (node (ref "J6") (pin "H1") (pinfunction "H1_H1") (pintype "bidirectional"))
      (node (ref "J6") (pin "J1") (pinfunction "J1_J1") (pintype "bidirectional"))
      (node (ref "J6") (pin "K1") (pinfunction "K1_K1") (pintype "bidirectional"))
    )
    (net (code "96") (name "unconnected-(D5D-C-Pad5)") (class "Default")
      (node (ref "D5") (pin "5") (pinfunction "C_5") (pintype "passive+no_connect"))
    )
    (net (code "97") (name "unconnected-(D6D-C-Pad5)") (class "Default")
      (node (ref "D6") (pin "5") (pinfunction "C_5") (pintype "passive+no_connect"))
    )
    (net (code "98") (name "unconnected-(J6-PadB1)") (class "Default")
      (node (ref "J6") (pin "B1") (pinfunction "B1_B1") (pintype "bidirectional+no_connect"))
    )
    (net (code "99") (name "unconnected-(J6-PadL2)") (class "Default")
      (node (ref "J6") (pin "L2") (pinfunction "L2_L2") (pintype "bidirectional+no_connect"))
    )
    (net (code "100") (name "unconnected-(J7-PadA3)") (class "Default")
      (node (ref "J7") (pin "A3") (pinfunction "A3_A3") (pintype "bidirectional+no_connect"))
    )
    (net (code "101") (name "unconnected-(J7-PadA5)") (class "Default")
      (node (ref "J7") (pin "A5") (pinfunction "A5_A5") (pintype "bidirectional+no_connect"))
    )
    (net (code "102") (name "unconnected-(J7-PadA7)") (class "Default")
      (node (ref "J7") (pin "A7") (pinfunction "A7_A7") (pintype "bidirectional+no_connect"))
    )
    (net (code "103") (name "unconnected-(J7-PadA8)") (class "Default")
      (node (ref "J7") (pin "A8") (pinfunction "A8_A8") (pintype "bidirectional+no_connect"))
    )
    (net (code "104") (name "unconnected-(J7-PadB2)") (class "Default")
      (node (ref "J7") (pin "B2") (pinfunction "B2_B2") (pintype "bidirectional+no_connect"))
    )
    (net (code "105") (name "unconnected-(J7-PadB3)") (class "Default")
      (node (ref "J7") (pin "B3") (pinfunction "B3_B3") (pintype "bidirectional+no_connect"))
    )
    (net (code "106") (name "unconnected-(J7-PadB4)") (class "Default")
      (node (ref "J7") (pin "B4") (pinfunction "B4_B4") (pintype "bidirectional+no_connect"))
    )
    (net (code "107") (name "unconnected-(J7-PadB5)") (class "Default")
      (node (ref "J7") (pin "B5") (pinfunction "B5_B5") (pintype "bidirectional+no_connect"))
    )
    (net (code "108") (name "unconnected-(J7-PadB6)") (class "Default")
      (node (ref "J7") (pin "B6") (pinfunction "B6_B6") (pintype "bidirectional+no_connect"))
    )
    (net (code "109") (name "unconnected-(J7-PadB7)") (class "Default")
      (node (ref "J7") (pin "B7") (pinfunction "B7_B7") (pintype "bidirectional+no_connect"))
    )
    (net (code "110") (name "unconnected-(J7-PadB8)") (class "Default")
      (node (ref "J7") (pin "B8") (pinfunction "B8_B8") (pintype "bidirectional+no_connect"))
    )
    (net (code "111") (name "unconnected-(J7-PadC2)") (class "Default")
      (node (ref "J7") (pin "C2") (pinfunction "C2_C2") (pintype "bidirectional+no_connect"))
    )
    (net (code "112") (name "unconnected-(J7-PadC4)") (class "Default")
      (node (ref "J7") (pin "C4") (pinfunction "C4_C4") (pintype "bidirectional+no_connect"))
    )
    (net (code "113") (name "unconnected-(J7-PadC6)") (class "Default")
      (node (ref "J7") (pin "C6") (pinfunction "C6_C6") (pintype "bidirectional+no_connect"))
    )
    (net (code "114") (name "unconnected-(J7-PadC8)") (class "Default")
      (node (ref "J7") (pin "C8") (pinfunction "C8_C8") (pintype "bidirectional+no_connect"))
    )
    (net (code "115") (name "unconnected-(J7-PadD3)") (class "Default")
      (node (ref "J7") (pin "D3") (pinfunction "D3_D3") (pintype "bidirectional+no_connect"))
    )
    (net (code "116") (name "unconnected-(J7-PadD5)") (class "Default")
      (node (ref "J7") (pin "D5") (pinfunction "D5_D5") (pintype "bidirectional+no_connect"))
    )
    (net (code "117") (name "unconnected-(J7-PadD7)") (class "Default")
      (node (ref "J7") (pin "D7") (pinfunction "D7_D7") (pintype "bidirectional+no_connect"))
    )
    (net (code "118") (name "unconnected-(J7-PadD8)") (class "Default")
      (node (ref "J7") (pin "D8") (pinfunction "D8_D8") (pintype "bidirectional+no_connect"))
    )
    (net (code "119") (name "unconnected-(J7-PadE2)") (class "Default")
      (node (ref "J7") (pin "E2") (pinfunction "E2_E2") (pintype "bidirectional+no_connect"))
    )
    (net (code "120") (name "unconnected-(J7-PadE3)") (class "Default")
      (node (ref "J7") (pin "E3") (pinfunction "E3_E3") (pintype "bidirectional+no_connect"))
    )
    (net (code "121") (name "unconnected-(J7-PadE4)") (class "Default")
      (node (ref "J7") (pin "E4") (pinfunction "E4_E4") (pintype "bidirectional+no_connect"))
    )
    (net (code "122") (name "unconnected-(J7-PadE5)") (class "Default")
      (node (ref "J7") (pin "E5") (pinfunction "E5_E5") (pintype "bidirectional+no_connect"))
    )
    (net (code "123") (name "unconnected-(J7-PadE6)") (class "Default")
      (node (ref "J7") (pin "E6") (pinfunction "E6_E6") (pintype "bidirectional+no_connect"))
    )
    (net (code "124") (name "unconnected-(J7-PadE7)") (class "Default")
      (node (ref "J7") (pin "E7") (pinfunction "E7_E7") (pintype "bidirectional+no_connect"))
    )
    (net (code "125") (name "unconnected-(J7-PadE8)") (class "Default")
      (node (ref "J7") (pin "E8") (pinfunction "E8_E8") (pintype "bidirectional+no_connect"))
    )
    (net (code "126") (name "unconnected-(J7-PadF2)") (class "Default")
      (node (ref "J7") (pin "F2") (pinfunction "F2_F2") (pintype "bidirectional+no_connect"))
    )
    (net (code "127") (name "unconnected-(J7-PadF4)") (class "Default")
      (node (ref "J7") (pin "F4") (pinfunction "F4_F4") (pintype "bidirectional+no_connect"))
    )
    (net (code "128") (name "unconnected-(J7-PadF6)") (class "Default")
      (node (ref "J7") (pin "F6") (pinfunction "F6_F6") (pintype "bidirectional+no_connect"))
    )
    (net (code "129") (name "unconnected-(J7-PadF8)") (class "Default")
      (node (ref "J7") (pin "F8") (pinfunction "F8_F8") (pintype "bidirectional+no_connect"))
    )
    (net (code "130") (name "unconnected-(J7-PadG3)") (class "Default")
      (node (ref "J7") (pin "G3") (pinfunction "G3_G3") (pintype "bidirectional+no_connect"))
    )
    (net (code "131") (name "unconnected-(J7-PadG5)") (class "Default")
      (node (ref "J7") (pin "G5") (pinfunction "G5_G5") (pintype "bidirectional+no_connect"))
    )
    (net (code "132") (name "unconnected-(J7-PadG7)") (class "Default")
      (node (ref "J7") (pin "G7") (pinfunction "G7_G7") (pintype "bidirectional+no_connect"))
    )
    (net (code "133") (name "unconnected-(J7-PadH2)") (class "Default")
      (node (ref "J7") (pin "H2") (pinfunction "H2_H2") (pintype "bidirectional+no_connect"))
    )
    (net (code "134") (name "unconnected-(J7-PadH3)") (class "Default")
      (node (ref "J7") (pin "H3") (pinfunction "H3_H3") (pintype "bidirectional+no_connect"))
    )
    (net (code "135") (name "unconnected-(J7-PadH4)") (class "Default")
      (node (ref "J7") (pin "H4") (pinfunction "H4_H4") (pintype "bidirectional+no_connect"))
    )
    (net (code "136") (name "unconnected-(J7-PadH5)") (class "Default")
      (node (ref "J7") (pin "H5") (pinfunction "H5_H5") (pintype "bidirectional+no_connect"))
    )
    (net (code "137") (name "unconnected-(J7-PadH6)") (class "Default")
      (node (ref "J7") (pin "H6") (pinfunction "H6_H6") (pintype "bidirectional+no_connect"))
    )
    (net (code "138") (name "unconnected-(J7-PadH7)") (class "Default")
      (node (ref "J7") (pin "H7") (pinfunction "H7_H7") (pintype "bidirectional+no_connect"))
    )
    (net (code "139") (name "unconnected-(J7-PadH8)") (class "Default")
      (node (ref "J7") (pin "H8") (pinfunction "H8_H8") (pintype "bidirectional+no_connect"))
    )
    (net (code "140") (name "unconnected-(J7-PadI2)") (class "Default")
      (node (ref "J7") (pin "I2") (pinfunction "I2_I2") (pintype "bidirectional+no_connect"))
    )
    (net (code "141") (name "unconnected-(J7-PadI4)") (class "Default")
      (node (ref "J7") (pin "I4") (pinfunction "I4_I4") (pintype "bidirectional+no_connect"))
    )
    (net (code "142") (name "unconnected-(J7-PadI6)") (class "Default")
      (node (ref "J7") (pin "I6") (pinfunction "I6_I6") (pintype "bidirectional+no_connect"))
    )
    (net (code "143") (name "unconnected-(J7-PadI8)") (class "Default")
      (node (ref "J7") (pin "I8") (pinfunction "I8_I8") (pintype "bidirectional+no_connect"))
    )
    (net (code "144") (name "unconnected-(J7-PadJ3)") (class "Default")
      (node (ref "J7") (pin "J3") (pinfunction "J3_J3") (pintype "bidirectional+no_connect"))
    )
    (net (code "145") (name "unconnected-(J7-PadJ5)") (class "Default")
      (node (ref "J7") (pin "J5") (pinfunction "J5_J5") (pintype "bidirectional+no_connect"))
    )
    (net (code "146") (name "unconnected-(J7-PadJ7)") (class "Default")
      (node (ref "J7") (pin "J7") (pinfunction "J7_J7") (pintype "bidirectional+no_connect"))
    )
    (net (code "147") (name "unconnected-(J7-PadK2)") (class "Default")
      (node (ref "J7") (pin "K2") (pinfunction "K2_K2") (pintype "bidirectional+no_connect"))
    )
    (net (code "148") (name "unconnected-(J7-PadK3)") (class "Default")
      (node (ref "J7") (pin "K3") (pinfunction "K3_K3") (pintype "bidirectional+no_connect"))
    )
    (net (code "149") (name "unconnected-(J7-PadK4)") (class "Default")
      (node (ref "J7") (pin "K4") (pinfunction "K4_K4") (pintype "bidirectional+no_connect"))
    )
    (net (code "150") (name "unconnected-(J7-PadK5)") (class "Default")
      (node (ref "J7") (pin "K5") (pinfunction "K5_K5") (pintype "bidirectional+no_connect"))
    )
    (net (code "151") (name "unconnected-(J7-PadK6)") (class "Default")
      (node (ref "J7") (pin "K6") (pinfunction "K6_K6") (pintype "bidirectional+no_connect"))
    )
    (net (code "152") (name "unconnected-(J7-PadK7)") (class "Default")
      (node (ref "J7") (pin "K7") (pinfunction "K7_K7") (pintype "bidirectional+no_connect"))
    )
    (net (code "153") (name "unconnected-(J7-PadK8)") (class "Default")
      (node (ref "J7") (pin "K8") (pinfunction "K8_K8") (pintype "bidirectional+no_connect"))
    )
    (net (code "154") (name "unconnected-(J7-PadL2)") (class "Default")
      (node (ref "J7") (pin "L2") (pinfunction "L2_L2") (pintype "bidirectional+no_connect"))
    )
    (net (code "155") (name "unconnected-(J7-PadL4)") (class "Default")
      (node (ref "J7") (pin "L4") (pinfunction "L4_L4") (pintype "bidirectional+no_connect"))
    )
    (net (code "156") (name "unconnected-(J7-PadL6)") (class "Default")
      (node (ref "J7") (pin "L6") (pinfunction "L6_L6") (pintype "bidirectional+no_connect"))
    )
    (net (code "157") (name "unconnected-(J7-PadL8)") (class "Default")
      (node (ref "J7") (pin "L8") (pinfunction "L8_L8") (pintype "bidirectional+no_connect"))
    )
  )
)
